# Color-LCD-Shield.net
KiCad netlist of a schematic drawn in EAGLE
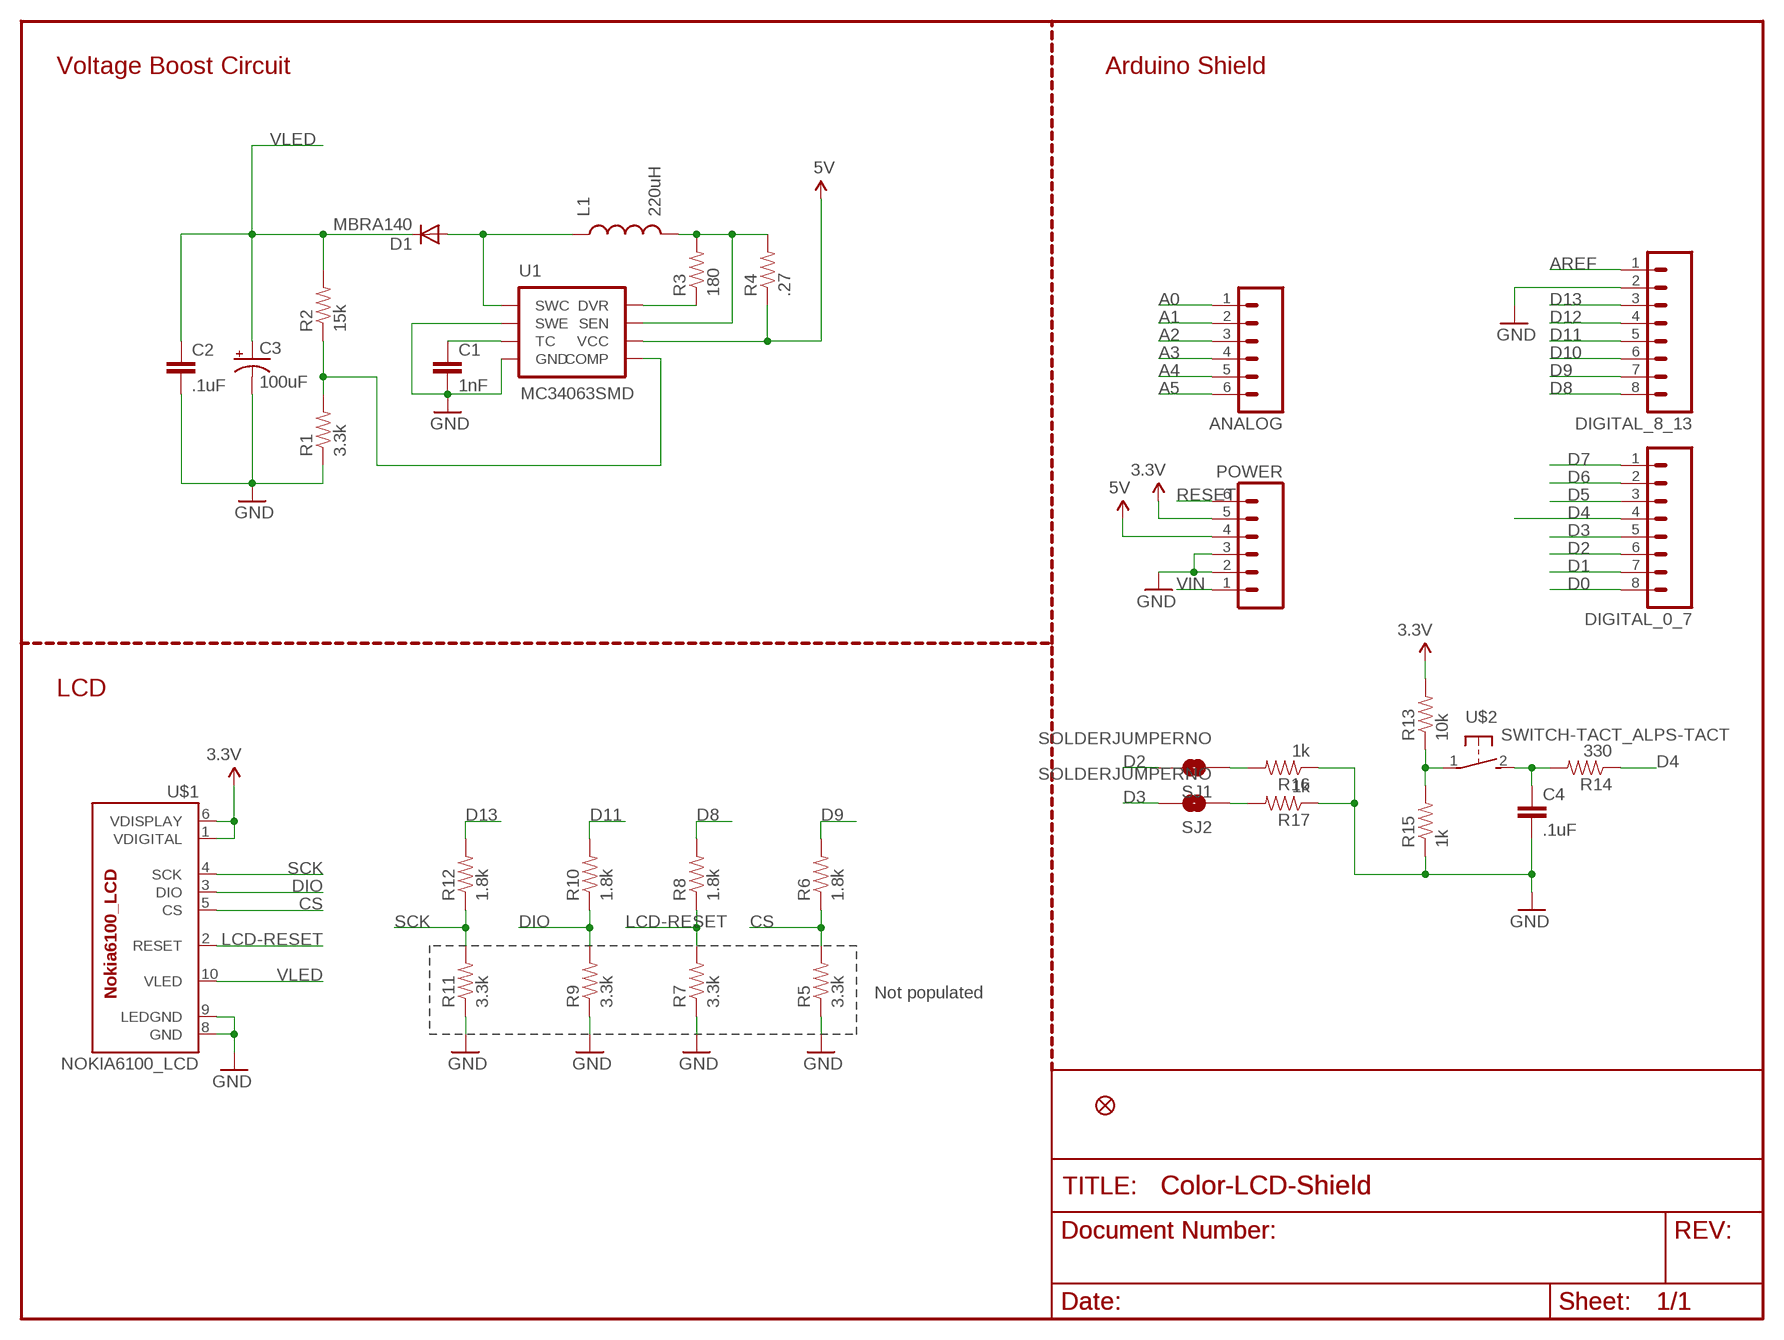
[diagram p0: schematic, sheet 1]

(export (version "E")
  (design (tool "Eeschema 10.0.6"))
  (components
    (comp (ref "ANALOG")
      (value "M06SIP")
      (footprint "eagle-import:1X06")
      (libsource (lib "eagle-import") (part "M06SIP"))
    )
    (comp (ref "C1")
      (value "1nF")
      (footprint "eagle-import:0603-CAP")
      (libsource (lib "eagle-import") (part "CAP0603-CAP"))
    )
    (comp (ref "C2")
      (value ".1uF")
      (footprint "eagle-import:0603-CAP")
      (libsource (lib "eagle-import") (part "CAP0603-CAP"))
    )
    (comp (ref "C3")
      (value "100uF")
      (footprint "eagle-import:EIA7343")
      (libsource (lib "eagle-import") (part "CAP_POL7343"))
    )
    (comp (ref "C4")
      (value ".1uF")
      (footprint "eagle-import:0603-CAP")
      (libsource (lib "eagle-import") (part "CAP0603-CAP"))
    )
    (comp (ref "D1")
      (value "MBRA140")
      (footprint "eagle-import:SMA-DIODE")
      (libsource (lib "eagle-import") (part "DIODESMA"))
    )
    (comp (ref "DIGITAL_0_7")
      (value "M08")
      (footprint "eagle-import:1X08")
      (libsource (lib "eagle-import") (part "M08"))
    )
    (comp (ref "DIGITAL_8_13")
      (value "M08")
      (footprint "eagle-import:1X08")
      (libsource (lib "eagle-import") (part "M08"))
    )
    (comp (ref "JP2")
      (value "FIDUCIAL1X2")
      (footprint "eagle-import:FIDUCIAL-1X2")
      (libsource (lib "eagle-import") (part "FIDUCIAL1X2"))
    )
    (comp (ref "L1")
      (value "220uH")
      (footprint "eagle-import:NPI75C")
      (libsource (lib "eagle-import") (part "INDUCTORNPI75C"))
    )
    (comp (ref "POWER")
      (value "M06SIP")
      (footprint "eagle-import:1X06")
      (libsource (lib "eagle-import") (part "M06SIP"))
    )
    (comp (ref "R1")
      (value "3.3k")
      (footprint "eagle-import:0603-RES")
      (libsource (lib "eagle-import") (part "RESISTOR0603-RES"))
    )
    (comp (ref "R2")
      (value "15k")
      (footprint "eagle-import:0603-RES")
      (libsource (lib "eagle-import") (part "RESISTOR0603-RES"))
    )
    (comp (ref "R3")
      (value "180")
      (footprint "eagle-import:0603-RES")
      (libsource (lib "eagle-import") (part "RESISTOR0603-RES"))
    )
    (comp (ref "R4")
      (value ".27")
      (footprint "eagle-import:0603-RES")
      (libsource (lib "eagle-import") (part "RESISTOR0603-RES"))
    )
    (comp (ref "R5")
      (value "3.3k")
      (footprint "eagle-import:0603-RES")
      (libsource (lib "eagle-import") (part "RESISTOR0603-RES"))
    )
    (comp (ref "R6")
      (value "1.8k")
      (footprint "eagle-import:0603-RES")
      (libsource (lib "eagle-import") (part "RESISTOR0603-RES"))
    )
    (comp (ref "R7")
      (value "3.3k")
      (footprint "eagle-import:0603-RES")
      (libsource (lib "eagle-import") (part "RESISTOR0603-RES"))
    )
    (comp (ref "R8")
      (value "1.8k")
      (footprint "eagle-import:0603-RES")
      (libsource (lib "eagle-import") (part "RESISTOR0603-RES"))
    )
    (comp (ref "R9")
      (value "3.3k")
      (footprint "eagle-import:0603-RES")
      (libsource (lib "eagle-import") (part "RESISTOR0603-RES"))
    )
    (comp (ref "R10")
      (value "1.8k")
      (footprint "eagle-import:0603-RES")
      (libsource (lib "eagle-import") (part "RESISTOR0603-RES"))
    )
    (comp (ref "R11")
      (value "3.3k")
      (footprint "eagle-import:0603-RES")
      (libsource (lib "eagle-import") (part "RESISTOR0603-RES"))
    )
    (comp (ref "R12")
      (value "1.8k")
      (footprint "eagle-import:0603-RES")
      (libsource (lib "eagle-import") (part "RESISTOR0603-RES"))
    )
    (comp (ref "R13")
      (value "10k")
      (footprint "eagle-import:0603-RES")
      (libsource (lib "eagle-import") (part "RESISTOR0603-RES"))
    )
    (comp (ref "R14")
      (value "330")
      (footprint "eagle-import:0603-RES")
      (libsource (lib "eagle-import") (part "RESISTOR0603-RES"))
    )
    (comp (ref "R15")
      (value "1k")
      (footprint "eagle-import:0603-RES")
      (libsource (lib "eagle-import") (part "RESISTOR0603-RES"))
    )
    (comp (ref "R16")
      (value "1k")
      (footprint "eagle-import:0603-RES")
      (libsource (lib "eagle-import") (part "RESISTOR0603-RES"))
    )
    (comp (ref "R17")
      (value "1k")
      (footprint "eagle-import:0603-RES")
      (libsource (lib "eagle-import") (part "RESISTOR0603-RES"))
    )
    (comp (ref "SJ1")
      (value "SOLDERJUMPERNO")
      (footprint "eagle-import:SJ_2S-NO")
      (libsource (lib "eagle-import") (part "SOLDERJUMPERNO"))
    )
    (comp (ref "SJ2")
      (value "SOLDERJUMPERNO")
      (footprint "eagle-import:SJ_2S-NO")
      (libsource (lib "eagle-import") (part "SOLDERJUMPERNO"))
    )
    (comp (ref "U$1")
      (value "NOKIA6100_LCD")
      (footprint "eagle-import:NOKIA6100_LCD")
      (libsource (lib "eagle-import") (part "NOKIA6100_LCD"))
    )
    (comp (ref "U$2")
      (value "SWITCH-TACT_ALPS-TACT")
      (footprint "eagle-import:SWITCH-TACT_DTS-6")
      (libsource (lib "eagle-import") (part "SWITCH-TACT_ALPS-TACT"))
    )
    (comp (ref "U1")
      (value "MC34063SMD")
      (footprint "eagle-import:SO08")
      (libsource (lib "eagle-import") (part "MC34063SMD"))
    )
  )
  (nets
    (net (code "1") (name "/A0") (class "Default")
      (node (ref "ANALOG") (pin "1") (pinfunction "1_1") (pintype "passive"))
    )
    (net (code "2") (name "/A1") (class "Default")
      (node (ref "ANALOG") (pin "2") (pinfunction "2_2") (pintype "passive"))
    )
    (net (code "3") (name "/A2") (class "Default")
      (node (ref "ANALOG") (pin "3") (pinfunction "3_3") (pintype "passive"))
    )
    (net (code "4") (name "/A3") (class "Default")
      (node (ref "ANALOG") (pin "4") (pinfunction "4_4") (pintype "passive"))
    )
    (net (code "5") (name "/A4") (class "Default")
      (node (ref "ANALOG") (pin "5") (pinfunction "5_5") (pintype "passive"))
    )
    (net (code "6") (name "/A5") (class "Default")
      (node (ref "ANALOG") (pin "6") (pinfunction "6_6") (pintype "passive"))
    )
    (net (code "7") (name "/AREF") (class "Default")
      (node (ref "DIGITAL_8_13") (pin "1") (pinfunction "1_1") (pintype "passive"))
    )
    (net (code "8") (name "/CS") (class "Default")
      (node (ref "R5") (pin "2") (pinfunction "2_2") (pintype "passive"))
      (node (ref "R6") (pin "1") (pinfunction "1_1") (pintype "passive"))
      (node (ref "U$1") (pin "5") (pinfunction "CS_5") (pintype "bidirectional"))
    )
    (net (code "9") (name "/D0") (class "Default")
      (node (ref "DIGITAL_0_7") (pin "8") (pinfunction "8_8") (pintype "passive"))
    )
    (net (code "10") (name "/D1") (class "Default")
      (node (ref "DIGITAL_0_7") (pin "7") (pinfunction "7_7") (pintype "passive"))
    )
    (net (code "11") (name "/D2") (class "Default")
      (node (ref "DIGITAL_0_7") (pin "6") (pinfunction "6_6") (pintype "passive"))
      (node (ref "SJ1") (pin "2") (pinfunction "2_2") (pintype "passive"))
    )
    (net (code "12") (name "/D3") (class "Default")
      (node (ref "DIGITAL_0_7") (pin "5") (pinfunction "5_5") (pintype "passive"))
      (node (ref "SJ2") (pin "2") (pinfunction "2_2") (pintype "passive"))
    )
    (net (code "13") (name "/D4") (class "Default")
      (node (ref "DIGITAL_0_7") (pin "4") (pinfunction "4_4") (pintype "passive"))
      (node (ref "R14") (pin "1") (pinfunction "1_1") (pintype "passive"))
    )
    (net (code "14") (name "/D5") (class "Default")
      (node (ref "DIGITAL_0_7") (pin "3") (pinfunction "3_3") (pintype "passive"))
    )
    (net (code "15") (name "/D6") (class "Default")
      (node (ref "DIGITAL_0_7") (pin "2") (pinfunction "2_2") (pintype "passive"))
    )
    (net (code "16") (name "/D7") (class "Default")
      (node (ref "DIGITAL_0_7") (pin "1") (pinfunction "1_1") (pintype "passive"))
    )
    (net (code "17") (name "/D8") (class "Default")
      (node (ref "DIGITAL_8_13") (pin "8") (pinfunction "8_8") (pintype "passive"))
      (node (ref "R8") (pin "2") (pinfunction "2_2") (pintype "passive"))
    )
    (net (code "18") (name "/D9") (class "Default")
      (node (ref "DIGITAL_8_13") (pin "7") (pinfunction "7_7") (pintype "passive"))
      (node (ref "R6") (pin "2") (pinfunction "2_2") (pintype "passive"))
    )
    (net (code "19") (name "/D10") (class "Default")
      (node (ref "DIGITAL_8_13") (pin "6") (pinfunction "6_6") (pintype "passive"))
    )
    (net (code "20") (name "/D11") (class "Default")
      (node (ref "DIGITAL_8_13") (pin "5") (pinfunction "5_5") (pintype "passive"))
      (node (ref "R10") (pin "2") (pinfunction "2_2") (pintype "passive"))
    )
    (net (code "21") (name "/D12") (class "Default")
      (node (ref "DIGITAL_8_13") (pin "4") (pinfunction "4_4") (pintype "passive"))
    )
    (net (code "22") (name "/D13") (class "Default")
      (node (ref "DIGITAL_8_13") (pin "3") (pinfunction "3_3") (pintype "passive"))
      (node (ref "R12") (pin "2") (pinfunction "2_2") (pintype "passive"))
    )
    (net (code "23") (name "/DIO") (class "Default")
      (node (ref "R10") (pin "1") (pinfunction "1_1") (pintype "passive"))
      (node (ref "R9") (pin "2") (pinfunction "2_2") (pintype "passive"))
      (node (ref "U$1") (pin "3") (pinfunction "DIO_3") (pintype "bidirectional"))
    )
    (net (code "24") (name "/LCD-RESET") (class "Default")
      (node (ref "R7") (pin "2") (pinfunction "2_2") (pintype "passive"))
      (node (ref "R8") (pin "1") (pinfunction "1_1") (pintype "passive"))
      (node (ref "U$1") (pin "2") (pinfunction "RESET_2") (pintype "bidirectional"))
    )
    (net (code "25") (name "/RESET") (class "Default")
      (node (ref "POWER") (pin "6") (pinfunction "6_6") (pintype "passive"))
    )
    (net (code "26") (name "/SCK") (class "Default")
      (node (ref "R11") (pin "2") (pinfunction "2_2") (pintype "passive"))
      (node (ref "R12") (pin "1") (pinfunction "1_1") (pintype "passive"))
      (node (ref "U$1") (pin "4") (pinfunction "SCK_4") (pintype "bidirectional"))
    )
    (net (code "27") (name "/VIN") (class "Default")
      (node (ref "POWER") (pin "1") (pinfunction "1_1") (pintype "passive"))
    )
    (net (code "28") (name "/VLED") (class "Default")
      (node (ref "C2") (pin "1") (pinfunction "1_1") (pintype "passive"))
      (node (ref "C3") (pin "A") (pinfunction "+_A") (pintype "passive"))
      (node (ref "D1") (pin "C") (pinfunction "C_C") (pintype "passive"))
      (node (ref "R2") (pin "2") (pinfunction "2_2") (pintype "passive"))
      (node (ref "U$1") (pin "10") (pinfunction "VLED_10") (pintype "bidirectional"))
    )
    (net (code "29") (name "3.3V") (class "Default")
      (node (ref "POWER") (pin "5") (pinfunction "5_5") (pintype "passive"))
      (node (ref "R13") (pin "2") (pinfunction "2_2") (pintype "passive"))
      (node (ref "U$1") (pin "1") (pinfunction "VDIGITAL_1") (pintype "bidirectional"))
      (node (ref "U$1") (pin "6") (pinfunction "VDISPLAY_6") (pintype "bidirectional"))
    )
    (net (code "30") (name "5V") (class "Default")
      (node (ref "POWER") (pin "4") (pinfunction "4_4") (pintype "passive"))
      (node (ref "R4") (pin "1") (pinfunction "1_1") (pintype "passive"))
      (node (ref "U1") (pin "6") (pinfunction "VCC_6") (pintype "bidirectional"))
    )
    (net (code "31") (name "GND") (class "Default")
      (node (ref "C1") (pin "2") (pinfunction "2_2") (pintype "passive"))
      (node (ref "C2") (pin "2") (pinfunction "2_2") (pintype "passive"))
      (node (ref "C3") (pin "C") (pinfunction "-_C") (pintype "passive"))
      (node (ref "C4") (pin "2") (pinfunction "2_2") (pintype "passive"))
      (node (ref "DIGITAL_8_13") (pin "2") (pinfunction "2_2") (pintype "passive"))
      (node (ref "POWER") (pin "2") (pinfunction "2_2") (pintype "passive"))
      (node (ref "POWER") (pin "3") (pinfunction "3_3") (pintype "passive"))
      (node (ref "R1") (pin "1") (pinfunction "1_1") (pintype "passive"))
      (node (ref "R11") (pin "1") (pinfunction "1_1") (pintype "passive"))
      (node (ref "R15") (pin "1") (pinfunction "1_1") (pintype "passive"))
      (node (ref "R16") (pin "1") (pinfunction "1_1") (pintype "passive"))
      (node (ref "R17") (pin "1") (pinfunction "1_1") (pintype "passive"))
      (node (ref "R5") (pin "1") (pinfunction "1_1") (pintype "passive"))
      (node (ref "R7") (pin "1") (pinfunction "1_1") (pintype "passive"))
      (node (ref "R9") (pin "1") (pinfunction "1_1") (pintype "passive"))
      (node (ref "U$1") (pin "8") (pinfunction "GND_8") (pintype "bidirectional"))
      (node (ref "U$1") (pin "9") (pinfunction "LEDGND_9") (pintype "bidirectional"))
      (node (ref "U1") (pin "2") (pinfunction "SWE_2") (pintype "bidirectional"))
      (node (ref "U1") (pin "4") (pinfunction "GND_4") (pintype "bidirectional"))
    )
    (net (code "32") (name "Net-(C4-Pad1)") (class "Default")
      (node (ref "C4") (pin "1") (pinfunction "1_1") (pintype "passive"))
      (node (ref "R14") (pin "2") (pinfunction "2_2") (pintype "passive"))
      (node (ref "U$2") (pin "2") (pinfunction "2_2") (pintype "passive"))
    )
    (net (code "33") (name "Net-(R13-Pad1)") (class "Default")
      (node (ref "R13") (pin "1") (pinfunction "1_1") (pintype "passive"))
      (node (ref "R15") (pin "2") (pinfunction "2_2") (pintype "passive"))
      (node (ref "U$2") (pin "1") (pinfunction "1_1") (pintype "passive"))
    )
    (net (code "34") (name "Net-(R16-Pad2)") (class "Default")
      (node (ref "R16") (pin "2") (pinfunction "2_2") (pintype "passive"))
      (node (ref "SJ1") (pin "1") (pinfunction "1_1") (pintype "passive"))
    )
    (net (code "35") (name "Net-(R17-Pad2)") (class "Default")
      (node (ref "R17") (pin "2") (pinfunction "2_2") (pintype "passive"))
      (node (ref "SJ2") (pin "1") (pinfunction "1_1") (pintype "passive"))
    )
    (net (code "36") (name "Net-(U1-COMP)") (class "Default")
      (node (ref "R1") (pin "2") (pinfunction "2_2") (pintype "passive"))
      (node (ref "R2") (pin "1") (pinfunction "1_1") (pintype "passive"))
      (node (ref "U1") (pin "5") (pinfunction "COMP_5") (pintype "bidirectional"))
    )
    (net (code "37") (name "Net-(U1-DVR)") (class "Default")
      (node (ref "R3") (pin "1") (pinfunction "1_1") (pintype "passive"))
      (node (ref "U1") (pin "8") (pinfunction "DVR_8") (pintype "bidirectional"))
    )
    (net (code "38") (name "Net-(U1-SEN)") (class "Default")
      (node (ref "L1") (pin "2") (pinfunction "2_2") (pintype "passive"))
      (node (ref "R3") (pin "2") (pinfunction "2_2") (pintype "passive"))
      (node (ref "R4") (pin "2") (pinfunction "2_2") (pintype "passive"))
      (node (ref "U1") (pin "7") (pinfunction "SEN_7") (pintype "bidirectional"))
    )
    (net (code "39") (name "Net-(U1-SWC)") (class "Default")
      (node (ref "D1") (pin "A") (pinfunction "A_A") (pintype "passive"))
      (node (ref "L1") (pin "1") (pinfunction "1_1") (pintype "passive"))
      (node (ref "U1") (pin "1") (pinfunction "SWC_1") (pintype "bidirectional"))
    )
    (net (code "40") (name "Net-(U1-TC)") (class "Default")
      (node (ref "C1") (pin "1") (pinfunction "1_1") (pintype "passive"))
      (node (ref "U1") (pin "3") (pinfunction "TC_3") (pintype "bidirectional"))
    )
  )
)
